# Schematic.net
KiCad netlist of a schematic drawn in EAGLE
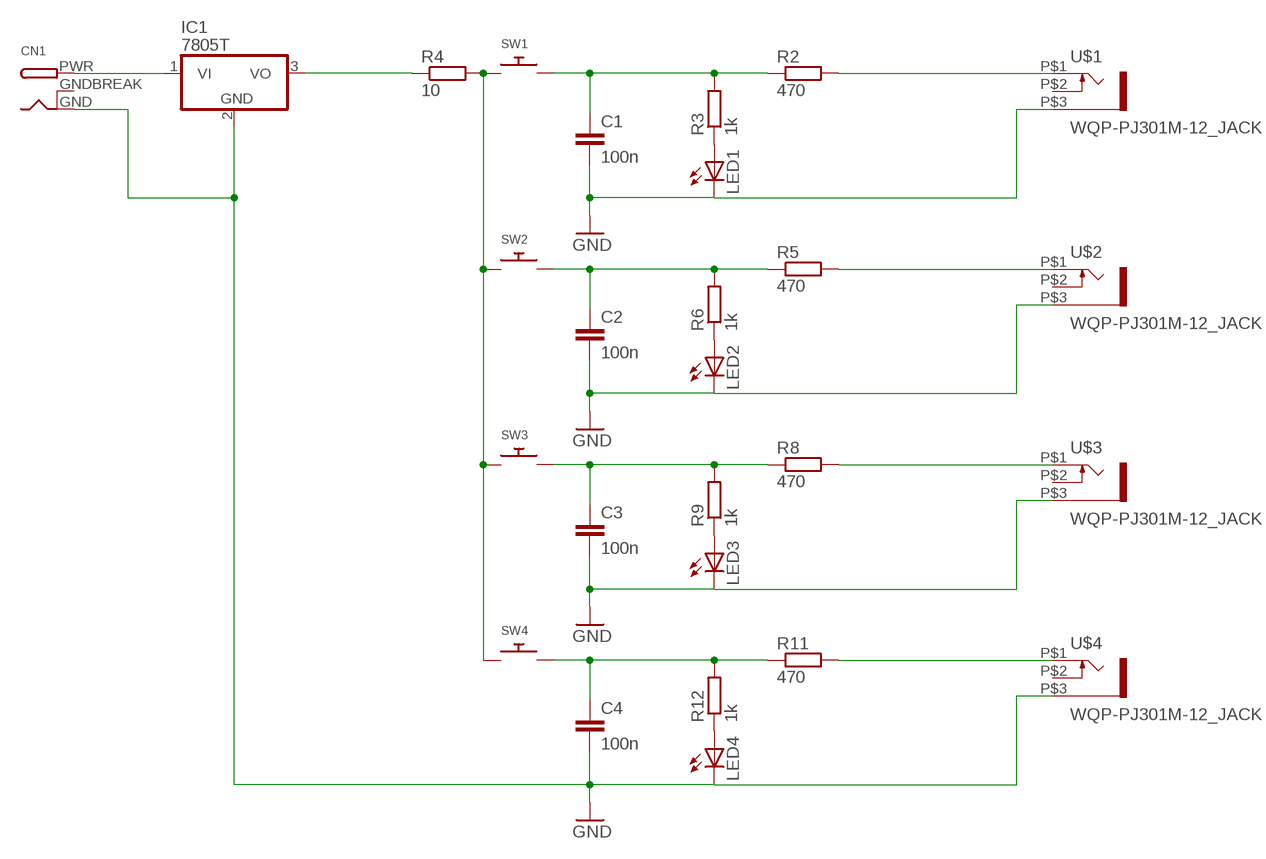
[diagram p0: schematic, sheet 1]

(export (version "E")
  (design (tool "Eeschema 10.0.6"))
  (components
    (comp (ref "C1")
      (value "100n")
      (footprint "eagle-import:C025-025X050")
      (libsource (lib "eagle-import") (part "C-EU025-025X050"))
    )
    (comp (ref "C2")
      (value "100n")
      (footprint "eagle-import:C025-025X050")
      (libsource (lib "eagle-import") (part "C-EU025-025X050"))
    )
    (comp (ref "C3")
      (value "100n")
      (footprint "eagle-import:C025-025X050")
      (libsource (lib "eagle-import") (part "C-EU025-025X050"))
    )
    (comp (ref "C4")
      (value "100n")
      (footprint "eagle-import:C025-025X050")
      (libsource (lib "eagle-import") (part "C-EU025-025X050"))
    )
    (comp (ref "CN1")
      (value "DCBARRELPTH")
      (footprint "eagle-import:DCJACK_2MM_PTH")
      (libsource (lib "eagle-import") (part "DCBARRELPTH"))
    )
    (comp (ref "IC1")
      (value "7805T")
      (footprint "eagle-import:TO220H")
      (libsource (lib "eagle-import") (part "78T05"))
    )
    (comp (ref "LED1")
      (value "LED5MM")
      (footprint "eagle-import:LED5MM")
      (libsource (lib "eagle-import") (part "LED5MM"))
    )
    (comp (ref "LED2")
      (value "LED5MM")
      (footprint "eagle-import:LED5MM")
      (libsource (lib "eagle-import") (part "LED5MM"))
    )
    (comp (ref "LED3")
      (value "LED5MM")
      (footprint "eagle-import:LED5MM")
      (libsource (lib "eagle-import") (part "LED5MM"))
    )
    (comp (ref "LED4")
      (value "LED5MM")
      (footprint "eagle-import:LED5MM")
      (libsource (lib "eagle-import") (part "LED5MM"))
    )
    (comp (ref "R2")
      (value "470")
      (footprint "eagle-import:0204_7")
      (libsource (lib "eagle-import") (part "R-EU_0204/7"))
    )
    (comp (ref "R3")
      (value "1k")
      (footprint "eagle-import:0204_7")
      (libsource (lib "eagle-import") (part "R-EU_0204/7"))
    )
    (comp (ref "R4")
      (value "10")
      (footprint "eagle-import:0204_7")
      (libsource (lib "eagle-import") (part "R-EU_0204/7"))
    )
    (comp (ref "R5")
      (value "470")
      (footprint "eagle-import:0204_7")
      (libsource (lib "eagle-import") (part "R-EU_0204/7"))
    )
    (comp (ref "R6")
      (value "1k")
      (footprint "eagle-import:0204_7")
      (libsource (lib "eagle-import") (part "R-EU_0204/7"))
    )
    (comp (ref "R8")
      (value "470")
      (footprint "eagle-import:0204_7")
      (libsource (lib "eagle-import") (part "R-EU_0204/7"))
    )
    (comp (ref "R9")
      (value "1k")
      (footprint "eagle-import:0204_7")
      (libsource (lib "eagle-import") (part "R-EU_0204/7"))
    )
    (comp (ref "R11")
      (value "470")
      (footprint "eagle-import:0204_7")
      (libsource (lib "eagle-import") (part "R-EU_0204/7"))
    )
    (comp (ref "R12")
      (value "1k")
      (footprint "eagle-import:0204_7")
      (libsource (lib "eagle-import") (part "R-EU_0204/7"))
    )
    (comp (ref "SW1")
      (value "SWITCH_PUSHBUTTONEVQ-PE")
      (footprint "eagle-import:TACT_PANA-EVQ")
      (libsource (lib "eagle-import") (part "SWITCH_PUSHBUTTONEVQ-PE"))
    )
    (comp (ref "SW2")
      (value "SWITCH_PUSHBUTTONEVQ-PE")
      (footprint "eagle-import:TACT_PANA-EVQ")
      (libsource (lib "eagle-import") (part "SWITCH_PUSHBUTTONEVQ-PE"))
    )
    (comp (ref "SW3")
      (value "SWITCH_PUSHBUTTONEVQ-PE")
      (footprint "eagle-import:TACT_PANA-EVQ")
      (libsource (lib "eagle-import") (part "SWITCH_PUSHBUTTONEVQ-PE"))
    )
    (comp (ref "SW4")
      (value "SWITCH_PUSHBUTTONEVQ-PE")
      (footprint "eagle-import:TACT_PANA-EVQ")
      (libsource (lib "eagle-import") (part "SWITCH_PUSHBUTTONEVQ-PE"))
    )
    (comp (ref "U$1")
      (value "WQP-PJ301M-12_JACK")
      (footprint "eagle-import:WQP-PJ301M-12_JACK")
      (libsource (lib "eagle-import") (part "WQP-PJ301M-12_JACK"))
    )
    (comp (ref "U$2")
      (value "WQP-PJ301M-12_JACK")
      (footprint "eagle-import:WQP-PJ301M-12_JACK")
      (libsource (lib "eagle-import") (part "WQP-PJ301M-12_JACK"))
    )
    (comp (ref "U$3")
      (value "WQP-PJ301M-12_JACK")
      (footprint "eagle-import:WQP-PJ301M-12_JACK")
      (libsource (lib "eagle-import") (part "WQP-PJ301M-12_JACK"))
    )
    (comp (ref "U$4")
      (value "WQP-PJ301M-12_JACK")
      (footprint "eagle-import:WQP-PJ301M-12_JACK")
      (libsource (lib "eagle-import") (part "WQP-PJ301M-12_JACK"))
    )
  )
  (nets
    (net (code "1") (name "/GNDBREAK") (class "Default")
      (node (ref "CN1") (pin "GNDBREAK") (pinfunction "GNDBREAK_GNDBREAK") (pintype "power_in"))
    )
    (net (code "2") (name "GND") (class "Default")
      (node (ref "C1") (pin "2") (pinfunction "2_2") (pintype "passive"))
      (node (ref "C2") (pin "2") (pinfunction "2_2") (pintype "passive"))
      (node (ref "C3") (pin "2") (pinfunction "2_2") (pintype "passive"))
      (node (ref "C4") (pin "2") (pinfunction "2_2") (pintype "passive"))
      (node (ref "CN1") (pin "GND") (pinfunction "GND_GND") (pintype "power_in"))
      (node (ref "IC1") (pin "2") (pinfunction "GND_2") (pintype "passive"))
      (node (ref "LED1") (pin "K") (pinfunction "C_K") (pintype "passive"))
      (node (ref "LED2") (pin "K") (pinfunction "C_K") (pintype "passive"))
      (node (ref "LED3") (pin "K") (pinfunction "C_K") (pintype "passive"))
      (node (ref "LED4") (pin "K") (pinfunction "C_K") (pintype "passive"))
      (node (ref "U$1") (pin "P$3") (pinfunction "1_P$3") (pintype "passive"))
      (node (ref "U$2") (pin "P$3") (pinfunction "1_P$3") (pintype "passive"))
      (node (ref "U$3") (pin "P$3") (pinfunction "1_P$3") (pintype "passive"))
      (node (ref "U$4") (pin "P$3") (pinfunction "1_P$3") (pintype "passive"))
    )
    (net (code "3") (name "Net-(C1-Pad1)") (class "Default")
      (node (ref "C1") (pin "1") (pinfunction "1_1") (pintype "passive"))
      (node (ref "R2") (pin "1") (pinfunction "1_1") (pintype "passive"))
      (node (ref "R3") (pin "2") (pinfunction "2_2") (pintype "passive"))
      (node (ref "SW1") (pin "P$2") (pinfunction "P$2_P$2") (pintype "passive"))
    )
    (net (code "4") (name "Net-(C2-Pad1)") (class "Default")
      (node (ref "C2") (pin "1") (pinfunction "1_1") (pintype "passive"))
      (node (ref "R5") (pin "1") (pinfunction "1_1") (pintype "passive"))
      (node (ref "R6") (pin "2") (pinfunction "2_2") (pintype "passive"))
      (node (ref "SW2") (pin "P$2") (pinfunction "P$2_P$2") (pintype "passive"))
    )
    (net (code "5") (name "Net-(C3-Pad1)") (class "Default")
      (node (ref "C3") (pin "1") (pinfunction "1_1") (pintype "passive"))
      (node (ref "R8") (pin "1") (pinfunction "1_1") (pintype "passive"))
      (node (ref "R9") (pin "2") (pinfunction "2_2") (pintype "passive"))
      (node (ref "SW3") (pin "P$2") (pinfunction "P$2_P$2") (pintype "passive"))
    )
    (net (code "6") (name "Net-(C4-Pad1)") (class "Default")
      (node (ref "C4") (pin "1") (pinfunction "1_1") (pintype "passive"))
      (node (ref "R11") (pin "1") (pinfunction "1_1") (pintype "passive"))
      (node (ref "R12") (pin "2") (pinfunction "2_2") (pintype "passive"))
      (node (ref "SW4") (pin "P$2") (pinfunction "P$2_P$2") (pintype "passive"))
    )
    (net (code "7") (name "Net-(IC1-VI)") (class "Default")
      (node (ref "CN1") (pin "PWR") (pinfunction "PWR_PWR") (pintype "power_in"))
      (node (ref "IC1") (pin "1") (pinfunction "VI_1") (pintype "input"))
    )
    (net (code "8") (name "Net-(IC1-VO)") (class "Default")
      (node (ref "IC1") (pin "3") (pinfunction "VO_3") (pintype "passive"))
      (node (ref "R4") (pin "1") (pinfunction "1_1") (pintype "passive"))
    )
    (net (code "9") (name "Net-(LED1-PadA)") (class "Default")
      (node (ref "LED1") (pin "A") (pinfunction "A_A") (pintype "passive"))
      (node (ref "R3") (pin "1") (pinfunction "1_1") (pintype "passive"))
    )
    (net (code "10") (name "Net-(LED2-PadA)") (class "Default")
      (node (ref "LED2") (pin "A") (pinfunction "A_A") (pintype "passive"))
      (node (ref "R6") (pin "1") (pinfunction "1_1") (pintype "passive"))
    )
    (net (code "11") (name "Net-(LED3-PadA)") (class "Default")
      (node (ref "LED3") (pin "A") (pinfunction "A_A") (pintype "passive"))
      (node (ref "R9") (pin "1") (pinfunction "1_1") (pintype "passive"))
    )
    (net (code "12") (name "Net-(LED4-PadA)") (class "Default")
      (node (ref "LED4") (pin "A") (pinfunction "A_A") (pintype "passive"))
      (node (ref "R12") (pin "1") (pinfunction "1_1") (pintype "passive"))
    )
    (net (code "13") (name "Net-(R4-Pad2)") (class "Default")
      (node (ref "R4") (pin "2") (pinfunction "2_2") (pintype "passive"))
      (node (ref "SW1") (pin "P$1") (pinfunction "P$1_P$1") (pintype "passive"))
      (node (ref "SW2") (pin "P$1") (pinfunction "P$1_P$1") (pintype "passive"))
      (node (ref "SW3") (pin "P$1") (pinfunction "P$1_P$1") (pintype "passive"))
      (node (ref "SW4") (pin "P$1") (pinfunction "P$1_P$1") (pintype "passive"))
    )
    (net (code "14") (name "Net-(U$1-2)") (class "Default")
      (node (ref "R2") (pin "2") (pinfunction "2_2") (pintype "passive"))
      (node (ref "U$1") (pin "P$1") (pinfunction "2_P$1") (pintype "passive"))
    )
    (net (code "15") (name "Net-(U$2-2)") (class "Default")
      (node (ref "R5") (pin "2") (pinfunction "2_2") (pintype "passive"))
      (node (ref "U$2") (pin "P$1") (pinfunction "2_P$1") (pintype "passive"))
    )
    (net (code "16") (name "Net-(U$3-2)") (class "Default")
      (node (ref "R8") (pin "2") (pinfunction "2_2") (pintype "passive"))
      (node (ref "U$3") (pin "P$1") (pinfunction "2_P$1") (pintype "passive"))
    )
    (net (code "17") (name "Net-(U$4-2)") (class "Default")
      (node (ref "R11") (pin "2") (pinfunction "2_2") (pintype "passive"))
      (node (ref "U$4") (pin "P$1") (pinfunction "2_P$1") (pintype "passive"))
    )
    (net (code "18") (name "unconnected-(U$1-3-PadP$2)") (class "Default")
      (node (ref "U$1") (pin "P$2") (pinfunction "3_P$2") (pintype "passive"))
    )
    (net (code "19") (name "unconnected-(U$2-3-PadP$2)") (class "Default")
      (node (ref "U$2") (pin "P$2") (pinfunction "3_P$2") (pintype "passive"))
    )
    (net (code "20") (name "unconnected-(U$3-3-PadP$2)") (class "Default")
      (node (ref "U$3") (pin "P$2") (pinfunction "3_P$2") (pintype "passive"))
    )
    (net (code "21") (name "unconnected-(U$4-3-PadP$2)") (class "Default")
      (node (ref "U$4") (pin "P$2") (pinfunction "3_P$2") (pintype "passive"))
    )
  )
)
